# Aux_PSU.net
KiCad netlist of a schematic drawn in Altium Designer
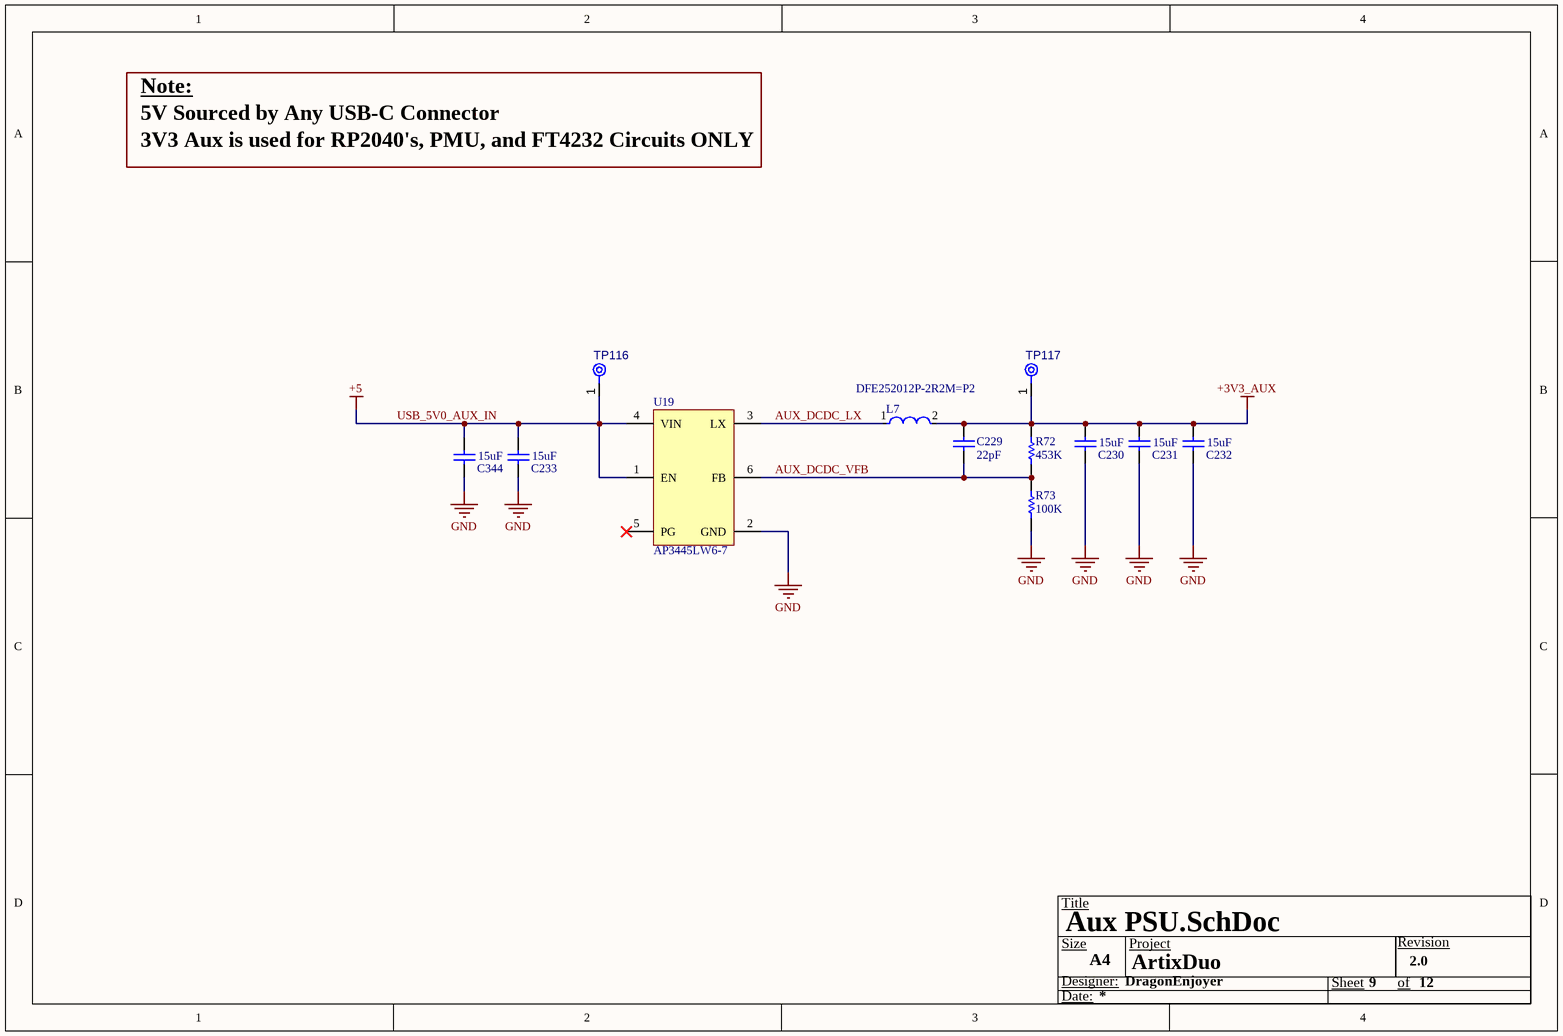
[diagram p0: Aux PSU.SchDoc]

(export (version "E")
  (design (tool "Eeschema 10.0.6"))
  (components
    (comp (ref "C229")
      (value "22pF")
      (footprint "CAPC1005X55X25ML05T05")
      (fields (field (name "MANUFACTURER") "Yageo") (field (name "TOLERANCE") "5%"))
      (libsource (lib "Altium Content Vault") (part "CAP-NP-2"))
    )
    (comp (ref "C230")
      (value "15uF")
      (footprint "CAPC0805(2012)145_L")
      (description "C Series 0805 15 uF 35 V ±20 % Tolerance X5R SMT Multilayer Ceramic Capacitor C2012X5R1V156M125AC")
      (libsource (lib "Main Workspace") (part "CAP-NP-2"))
    )
    (comp (ref "C231")
      (value "15uF")
      (footprint "CAPC0805(2012)145_L")
      (description "C Series 0805 15 uF 35 V ±20 % Tolerance X5R SMT Multilayer Ceramic Capacitor C2012X5R1V156M125AC")
      (libsource (lib "Main Workspace") (part "CAP-NP-2"))
    )
    (comp (ref "C232")
      (value "15uF")
      (footprint "CAPC0805(2012)145_L")
      (description "C Series 0805 15 uF 35 V ±20 % Tolerance X5R SMT Multilayer Ceramic Capacitor C2012X5R1V156M125AC")
      (libsource (lib "Main Workspace") (part "CAP-NP-2"))
    )
    (comp (ref "C233")
      (value "15uF")
      (footprint "CAPC0805(2012)145_L")
      (description "C Series 0805 15 uF 35 V ±20 % Tolerance X5R SMT Multilayer Ceramic Capacitor C2012X5R1V156M125AC")
      (libsource (lib "Main Workspace") (part "CAP-NP-2"))
    )
    (comp (ref "C344")
      (value "15uF")
      (footprint "CAPC0805(2012)145_L")
      (description "C Series 0805 15 uF 35 V ±20 % Tolerance X5R SMT Multilayer Ceramic Capacitor C2012X5R1V156M125AC")
      (libsource (lib "Main Workspace") (part "CAP-NP-2"))
    )
    (comp (ref "L7")
      (value "DFE252012P-2R2M=P2")
      (footprint "FP-DFE252012C-MFG")
      (description "Shielded Wirewound Inductor 2.2uH 20% 2200mA 0.084Ω 1008 (2520)")
      (fields (field (name "TOLERANCE") "20%"))
      (libsource (lib "Altium Content Vault") (part "725321dda6339637d4d059423bc1c3c"))
    )
    (comp (ref "R72")
      (value "453K")
      (footprint "RESC1005X40X25NL05T10")
      (description "RC0402FR-07453KL")
      (fields (field (name "MANUFACTURER") "Yageo"))
      (libsource (lib "Altium Content Vault") (part "RES"))
    )
    (comp (ref "R73")
      (value "100K")
      (footprint "RESC1005X40X25NL05T10")
      (description "RC0402FR-07100KL")
      (fields (field (name "MANUFACTURER") "Yageo / Phycomp"))
      (libsource (lib "Altium Content Vault") (part "RES"))
    )
    (comp (ref "TP116")
      (value "TPAD6R")
      (footprint "TP06R")
      (description "0.6mm round")
      (libsource (lib "Main Workspace") (part "CMP-001-0001-4"))
    )
    (comp (ref "TP117")
      (value "TPAD6R")
      (footprint "TP06R")
      (description "0.6mm round")
      (libsource (lib "Main Workspace") (part "CMP-001-0001-4"))
    )
    (comp (ref "U19")
      (value "AP3445LW6-7")
      (footprint "SOT95P245X130-6N")
      (description "AP3445 Series 5.5 V 2 A 588 mW Surface Mount Buck Switching Regulator - SOT-23-6")
      (libsource (lib "Main Workspace") (part "AP3445LW6-7"))
    )
  )
  (nets
    (net (code "1") (name "+3V3_AUX") (class "Default")
      (node (ref "C229") (pin "2") (pinfunction "2_2") (pintype "passive"))
      (node (ref "C230") (pin "2") (pinfunction "2_2") (pintype "passive"))
      (node (ref "C231") (pin "2") (pinfunction "2_2") (pintype "passive"))
      (node (ref "C232") (pin "2") (pinfunction "2_2") (pintype "passive"))
      (node (ref "L7") (pin "2") (pinfunction "2_2") (pintype "passive"))
      (node (ref "R72") (pin "2") (pinfunction "2_2") (pintype "passive"))
      (node (ref "TP117") (pin "1") (pinfunction "TP_1") (pintype "passive"))
    )
    (net (code "2") (name "+5") (class "Default")
      (node (ref "C233") (pin "2") (pinfunction "2_2") (pintype "passive"))
      (node (ref "C344") (pin "2") (pinfunction "2_2") (pintype "passive"))
      (node (ref "TP116") (pin "1") (pinfunction "TP_1") (pintype "passive"))
      (node (ref "U19") (pin "1") (pinfunction "EN_1") (pintype "passive"))
      (node (ref "U19") (pin "4") (pinfunction "VIN_4") (pintype "passive"))
    )
    (net (code "3") (name "/AUX_DCDC_LX") (class "Default")
      (node (ref "L7") (pin "1") (pinfunction "1_1") (pintype "passive"))
      (node (ref "U19") (pin "3") (pinfunction "LX_3") (pintype "passive"))
    )
    (net (code "4") (name "/AUX_DCDC_VFB") (class "Default")
      (node (ref "C229") (pin "1") (pinfunction "1_1") (pintype "passive"))
      (node (ref "R72") (pin "1") (pinfunction "1_1") (pintype "passive"))
      (node (ref "R73") (pin "2") (pinfunction "2_2") (pintype "passive"))
      (node (ref "U19") (pin "6") (pinfunction "FB_6") (pintype "passive"))
    )
    (net (code "5") (name "GND") (class "Default")
      (node (ref "C230") (pin "1") (pinfunction "1_1") (pintype "passive"))
      (node (ref "C231") (pin "1") (pinfunction "1_1") (pintype "passive"))
      (node (ref "C232") (pin "1") (pinfunction "1_1") (pintype "passive"))
      (node (ref "C233") (pin "1") (pinfunction "1_1") (pintype "passive"))
      (node (ref "C344") (pin "1") (pinfunction "1_1") (pintype "passive"))
      (node (ref "R73") (pin "1") (pinfunction "1_1") (pintype "passive"))
      (node (ref "U19") (pin "2") (pinfunction "GND_2") (pintype "passive"))
    )
    (net (code "6") (name "unconnected-(U19-PG-Pad5)") (class "Default")
      (node (ref "U19") (pin "5") (pinfunction "PG_5") (pintype "passive+no_connect"))
    )
  )
)
